# ChargerLED_Base.net
KiCad netlist of a schematic drawn in EAGLE
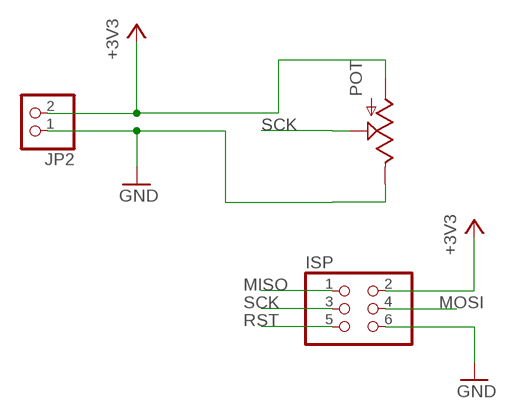
[diagram p0: schematic, sheet 1]

(export (version "E")
  (design (tool "Eeschema 10.0.6"))
  (components
    (comp (ref "ISP")
      (value "PINHD-2X3")
      (footprint "eagle-import:2X03")
      (libsource (lib "eagle-import") (part "PINHD-2X3"))
    )
    (comp (ref "JP2")
      (value "PINHD-1X2/90")
      (footprint "eagle-import:1X02_90")
      (libsource (lib "eagle-import") (part "PINHD-1X2/90"))
    )
    (comp (ref "POT")
      (value "POT-RV16AF-20")
      (footprint "eagle-import:POT_ALPHA_RV16AF-20")
      (libsource (lib "eagle-import") (part "POT-RV16AF-20"))
    )
  )
  (nets
    (net (code "1") (name "+3V3") (class "Default")
      (node (ref "ISP") (pin "2") (pinfunction "2_2") (pintype "passive"))
      (node (ref "JP2") (pin "2") (pinfunction "2_2") (pintype "passive"))
      (node (ref "POT") (pin "1") (pinfunction "A_1") (pintype "passive"))
    )
    (net (code "2") (name "/MISO") (class "Default")
      (node (ref "ISP") (pin "1") (pinfunction "1_1") (pintype "passive"))
    )
    (net (code "3") (name "/MOSI") (class "Default")
      (node (ref "ISP") (pin "4") (pinfunction "4_4") (pintype "passive"))
    )
    (net (code "4") (name "/RST") (class "Default")
      (node (ref "ISP") (pin "5") (pinfunction "5_5") (pintype "passive"))
    )
    (net (code "5") (name "/SCK") (class "Default")
      (node (ref "ISP") (pin "3") (pinfunction "3_3") (pintype "passive"))
      (node (ref "POT") (pin "2") (pinfunction "S_2") (pintype "passive"))
    )
    (net (code "6") (name "GND") (class "Default")
      (node (ref "ISP") (pin "6") (pinfunction "6_6") (pintype "passive"))
      (node (ref "JP2") (pin "1") (pinfunction "1_1") (pintype "passive"))
      (node (ref "POT") (pin "3") (pinfunction "E_3") (pintype "passive"))
    )
  )
)
